# irkit_periph_lightFilter_v02.net
KiCad netlist of a schematic drawn in EAGLE
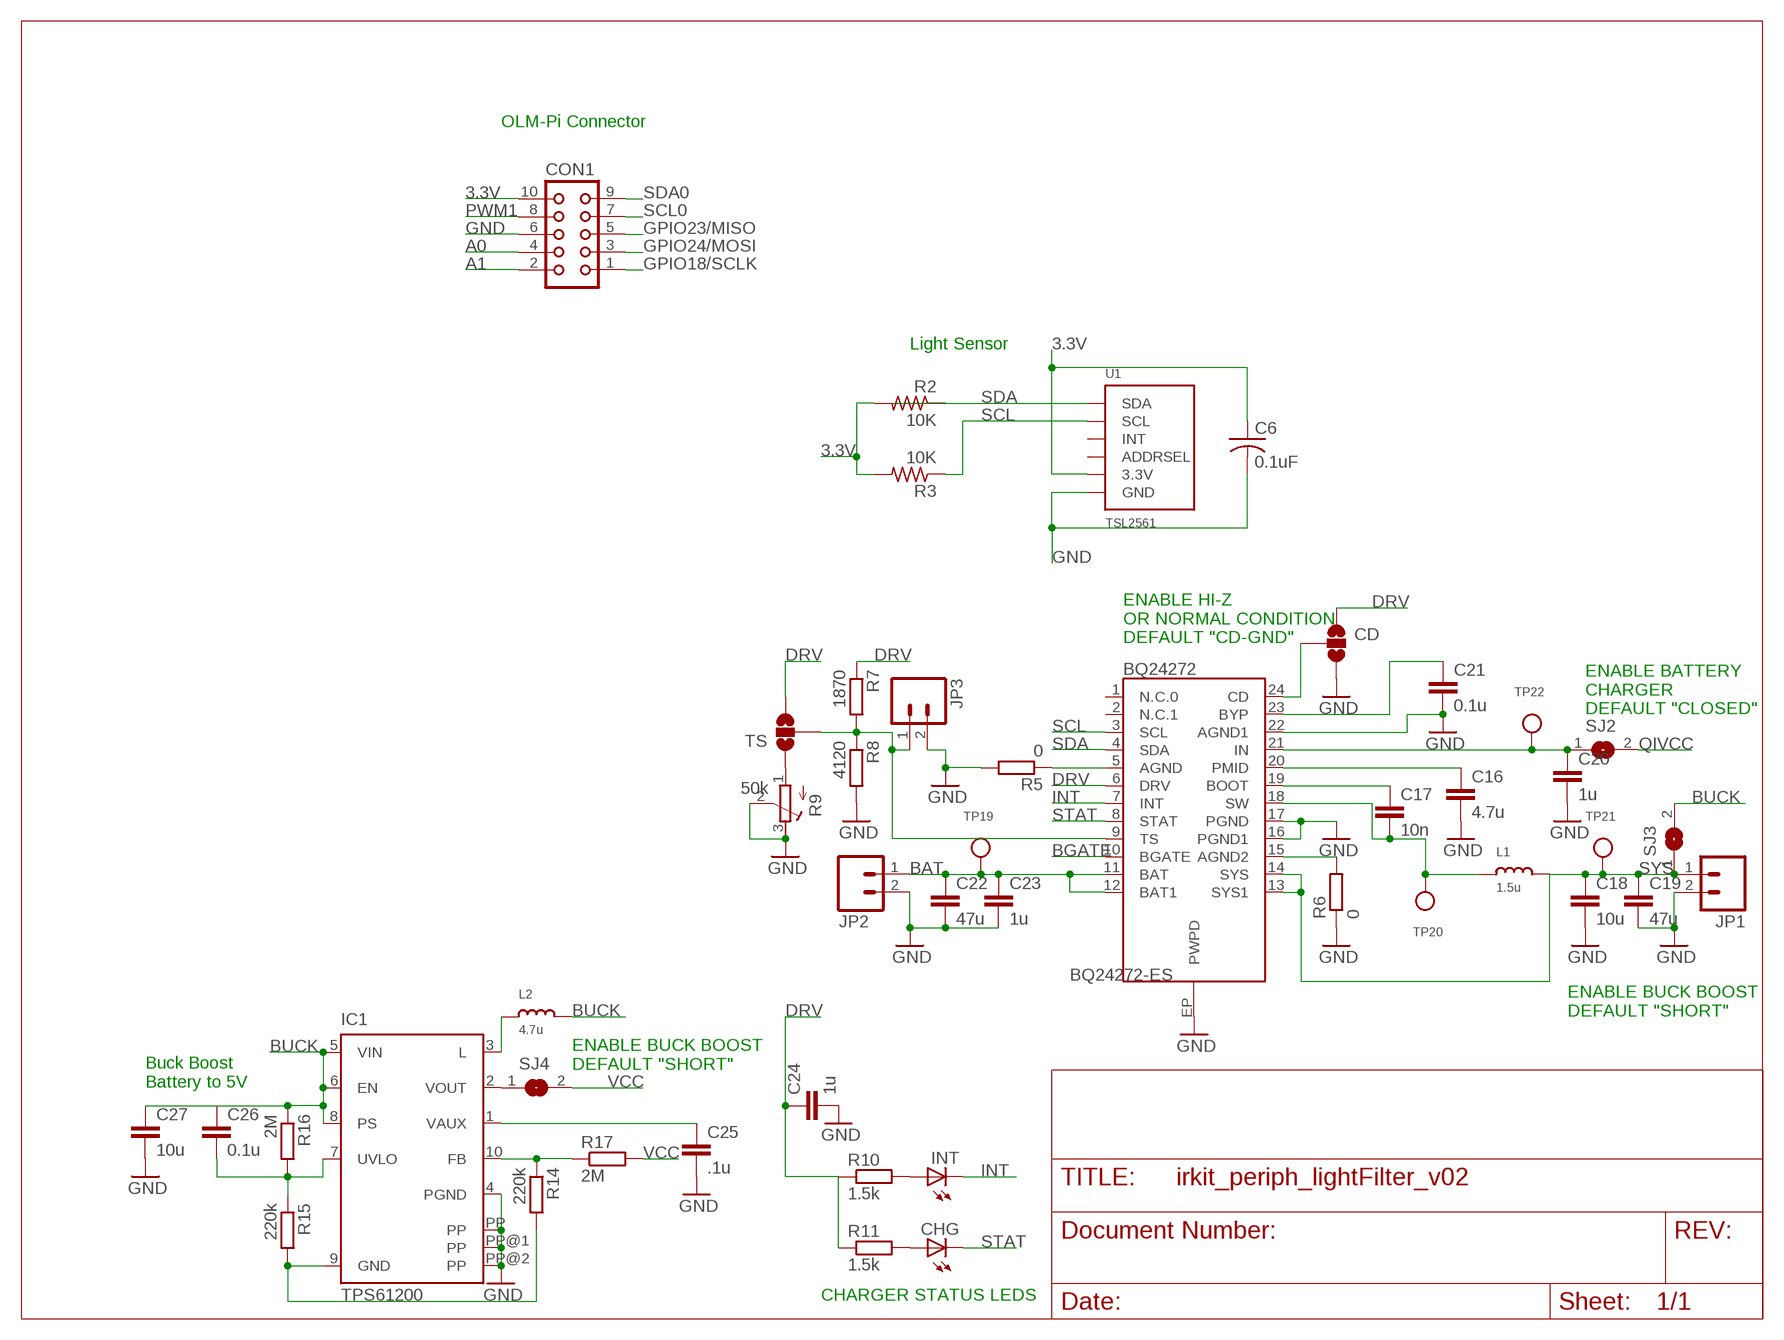
[diagram p0: schematic, sheet 1]

(export (version "E")
  (design (tool "Eeschema 10.0.6"))
  (components
    (comp (ref "BQ24272")
      (value "BQ24272-ES")
      (footprint "eagle-import:QFN-24_ALT2")
      (libsource (lib "eagle-import") (part "BQ24272-ES"))
    )
    (comp (ref "C6")
      (value "0.1uF")
      (footprint "eagle-import:C0805")
      (libsource (lib "eagle-import") (part "C-USC0805"))
    )
    (comp (ref "C16")
      (value "4.7u")
      (footprint "eagle-import:C0603K")
      (libsource (lib "eagle-import") (part "C-EUC0603K"))
    )
    (comp (ref "C17")
      (value "10n")
      (footprint "eagle-import:C0603K")
      (libsource (lib "eagle-import") (part "C-EUC0603K"))
    )
    (comp (ref "C18")
      (value "10u")
      (footprint "eagle-import:C0603K")
      (libsource (lib "eagle-import") (part "C-EUC0603K"))
    )
    (comp (ref "C19")
      (value "47u")
      (footprint "eagle-import:C0603K")
      (libsource (lib "eagle-import") (part "C-EUC0603K"))
    )
    (comp (ref "C20")
      (value "1u")
      (footprint "eagle-import:C0603K")
      (libsource (lib "eagle-import") (part "C-EUC0603K"))
    )
    (comp (ref "C21")
      (value "0.1u")
      (footprint "eagle-import:C0603K")
      (libsource (lib "eagle-import") (part "C-EUC0603K"))
    )
    (comp (ref "C22")
      (value "47u")
      (footprint "eagle-import:C0603K")
      (libsource (lib "eagle-import") (part "C-EUC0603K"))
    )
    (comp (ref "C23")
      (value "1u")
      (footprint "eagle-import:C0603K")
      (libsource (lib "eagle-import") (part "C-EUC0603K"))
    )
    (comp (ref "C24")
      (value "1u")
      (footprint "eagle-import:C0603K")
      (libsource (lib "eagle-import") (part "C-EUC0603K"))
    )
    (comp (ref "C25")
      (value ".1u")
      (footprint "eagle-import:C0603K")
      (libsource (lib "eagle-import") (part "C-EUC0603K"))
    )
    (comp (ref "C26")
      (value "0.1u")
      (footprint "eagle-import:C0603K")
      (libsource (lib "eagle-import") (part "C-EUC0603K"))
    )
    (comp (ref "C27")
      (value "10u")
      (footprint "eagle-import:C0603K")
      (libsource (lib "eagle-import") (part "C-EUC0603K"))
    )
    (comp (ref "CD")
      (value "SOLDERJUMPER_2WAYS")
      (footprint "eagle-import:SJ_3")
      (libsource (lib "eagle-import") (part "SOLDERJUMPER_2WAYS"))
    )
    (comp (ref "CHG")
      (value "LEDCHIP-LED0603")
      (footprint "eagle-import:CHIP-LED0603")
      (libsource (lib "eagle-import") (part "LEDCHIP-LED0603"))
    )
    (comp (ref "CON1")
      (value "CON10L")
      (footprint "eagle-import:CON10L")
      (libsource (lib "eagle-import") (part "CON10L"))
    )
    (comp (ref "IC1")
      (value "TPS61200")
      (footprint "eagle-import:S-PDSO-N10")
      (fields (field (name "MPN") "TPS61200DRCT"))
      (libsource (lib "eagle-import") (part "TPS61200"))
    )
    (comp (ref "INT")
      (value "LEDCHIP-LED0603")
      (footprint "eagle-import:CHIP-LED0603")
      (libsource (lib "eagle-import") (part "LEDCHIP-LED0603"))
    )
    (comp (ref "JP1")
      (value "M02PTH3")
      (footprint "eagle-import:1X02_LONGPADS")
      (libsource (lib "eagle-import") (part "M02PTH3"))
    )
    (comp (ref "JP2")
      (value "M02PTH3")
      (footprint "eagle-import:1X02_LONGPADS")
      (libsource (lib "eagle-import") (part "M02PTH3"))
    )
    (comp (ref "JP3")
      (value "M02PTH3")
      (footprint "eagle-import:1X02_LONGPADS")
      (libsource (lib "eagle-import") (part "M02PTH3"))
    )
    (comp (ref "L1")
      (value "1.5u")
      (footprint "eagle-import:INDUCTOR_5X5MM_NR5040_NOTHERMALS")
      (libsource (lib "eagle-import") (part "INDUCTORNR5040"))
    )
    (comp (ref "L2")
      (value "4.7u")
      (footprint "eagle-import:INDUCTOR_5X5MM_NR5040_NOTHERMALS")
      (libsource (lib "eagle-import") (part "INDUCTORNR5040"))
    )
    (comp (ref "R2")
      (value "10K")
      (footprint "eagle-import:R0805")
      (libsource (lib "eagle-import") (part "R-US_R0805"))
    )
    (comp (ref "R3")
      (value "10K")
      (footprint "eagle-import:R0805")
      (libsource (lib "eagle-import") (part "R-US_R0805"))
    )
    (comp (ref "R5")
      (value "0")
      (footprint "eagle-import:R0402")
      (fields (field (name "MPN") "ERJ3EKF3000V"))
      (libsource (lib "eagle-import") (part "R-EU_R0402"))
    )
    (comp (ref "R6")
      (value "0")
      (footprint "eagle-import:R0402")
      (fields (field (name "MPN") "ERJ3EKF3000V"))
      (libsource (lib "eagle-import") (part "R-EU_R0402"))
    )
    (comp (ref "R7")
      (value "1870")
      (footprint "eagle-import:R0402")
      (fields (field (name "MPN") "ERJ3EKF3000V"))
      (libsource (lib "eagle-import") (part "R-EU_R0402"))
    )
    (comp (ref "R8")
      (value "4120")
      (footprint "eagle-import:R0402")
      (fields (field (name "MPN") "ERJ3EKF3000V"))
      (libsource (lib "eagle-import") (part "R-EU_R0402"))
    )
    (comp (ref "R9")
      (value "50k")
      (footprint "eagle-import:RTRIM64Y")
      (libsource (lib "eagle-import") (part "R-TRIMM64Y"))
    )
    (comp (ref "R10")
      (value "1.5k")
      (footprint "eagle-import:R0402")
      (fields (field (name "MPN") "ERJ3EKF3000V"))
      (libsource (lib "eagle-import") (part "R-EU_R0402"))
    )
    (comp (ref "R11")
      (value "1.5k")
      (footprint "eagle-import:R0402")
      (fields (field (name "MPN") "ERJ3EKF3000V"))
      (libsource (lib "eagle-import") (part "R-EU_R0402"))
    )
    (comp (ref "R14")
      (value "220k")
      (footprint "eagle-import:R0402")
      (fields (field (name "MPN") "ERJ3EKF3000V"))
      (libsource (lib "eagle-import") (part "R-EU_R0402"))
    )
    (comp (ref "R15")
      (value "220k")
      (footprint "eagle-import:R0402")
      (fields (field (name "MPN") "ERJ3EKF3000V"))
      (libsource (lib "eagle-import") (part "R-EU_R0402"))
    )
    (comp (ref "R16")
      (value "2M")
      (footprint "eagle-import:R0402")
      (fields (field (name "MPN") "ERJ3EKF3000V"))
      (libsource (lib "eagle-import") (part "R-EU_R0402"))
    )
    (comp (ref "R17")
      (value "2M")
      (footprint "eagle-import:R0402")
      (fields (field (name "MPN") "ERJ3EKF3000V"))
      (libsource (lib "eagle-import") (part "R-EU_R0402"))
    )
    (comp (ref "SJ2") (value "SJ") (footprint "eagle-import:SJ") (libsource (lib "eagle-import") (part "SJ")))
    (comp (ref "SJ3") (value "SJ") (footprint "eagle-import:SJ") (libsource (lib "eagle-import") (part "SJ")))
    (comp (ref "SJ4") (value "SJ") (footprint "eagle-import:SJ") (libsource (lib "eagle-import") (part "SJ")))
    (comp (ref "TP19")
      (value "TESTPOINTROUND1MM")
      (footprint "eagle-import:TESTPOINT_ROUND_1MM")
      (libsource (lib "eagle-import") (part "TESTPOINTROUND1MM"))
    )
    (comp (ref "TP20")
      (value "TESTPOINTROUND1MM")
      (footprint "eagle-import:TESTPOINT_ROUND_1MM")
      (libsource (lib "eagle-import") (part "TESTPOINTROUND1MM"))
    )
    (comp (ref "TP21")
      (value "TESTPOINTROUND1MM")
      (footprint "eagle-import:TESTPOINT_ROUND_1MM")
      (libsource (lib "eagle-import") (part "TESTPOINTROUND1MM"))
    )
    (comp (ref "TP22")
      (value "TESTPOINTROUND1MM")
      (footprint "eagle-import:TESTPOINT_ROUND_1MM")
      (libsource (lib "eagle-import") (part "TESTPOINTROUND1MM"))
    )
    (comp (ref "TS")
      (value "SOLDERJUMPER_2WAYS")
      (footprint "eagle-import:SJ_3")
      (libsource (lib "eagle-import") (part "SOLDERJUMPER_2WAYS"))
    )
    (comp (ref "U1")
      (value "TSL2561")
      (footprint "eagle-import:TSL2561_FN")
      (libsource (lib "eagle-import") (part "TSL2561"))
    )
  )
  (nets
    (net (code "1") (name "/3.3V") (class "Default")
      (node (ref "C6") (pin "1") (pinfunction "1_1") (pintype "passive"))
      (node (ref "CON1") (pin "10") (pinfunction "10_10") (pintype "passive"))
      (node (ref "R2") (pin "2") (pinfunction "2_2") (pintype "passive"))
      (node (ref "R3") (pin "2") (pinfunction "2_2") (pintype "passive"))
      (node (ref "U1") (pin "VDD") (pinfunction "3.3V_VDD") (pintype "bidirectional"))
    )
    (net (code "2") (name "/A0") (class "Default")
      (node (ref "CON1") (pin "4") (pinfunction "4_4") (pintype "passive"))
    )
    (net (code "3") (name "/A1") (class "Default")
      (node (ref "CON1") (pin "2") (pinfunction "2_2") (pintype "passive"))
    )
    (net (code "4") (name "/BAT") (class "Default")
      (node (ref "BQ24272") (pin "11") (pinfunction "BAT_11") (pintype "bidirectional"))
      (node (ref "BQ24272") (pin "12") (pinfunction "BAT1_12") (pintype "bidirectional"))
      (node (ref "C22") (pin "1") (pinfunction "1_1") (pintype "passive"))
      (node (ref "C23") (pin "1") (pinfunction "1_1") (pintype "passive"))
      (node (ref "JP2") (pin "1") (pinfunction "1_1") (pintype "passive"))
      (node (ref "TP19") (pin "P$1") (pinfunction "P$1_P$1") (pintype "bidirectional"))
    )
    (net (code "5") (name "/BGATE") (class "Default")
      (node (ref "BQ24272") (pin "10") (pinfunction "BGATE_10") (pintype "bidirectional"))
    )
    (net (code "6") (name "/BUCK") (class "Default")
      (node (ref "C26") (pin "1") (pinfunction "1_1") (pintype "passive"))
      (node (ref "C27") (pin "1") (pinfunction "1_1") (pintype "passive"))
      (node (ref "IC1") (pin "5") (pinfunction "VIN_5") (pintype "input"))
      (node (ref "IC1") (pin "6") (pinfunction "EN_6") (pintype "input"))
      (node (ref "IC1") (pin "8") (pinfunction "PS_8") (pintype "input"))
      (node (ref "L2") (pin "P$2") (pinfunction "2_P$2") (pintype "passive"))
      (node (ref "R16") (pin "1") (pinfunction "1_1") (pintype "passive"))
      (node (ref "SJ3") (pin "2") (pinfunction "2_2") (pintype "passive"))
    )
    (net (code "7") (name "/DRV") (class "Default")
      (node (ref "BQ24272") (pin "6") (pinfunction "DRV_6") (pintype "bidirectional"))
      (node (ref "C24") (pin "1") (pinfunction "1_1") (pintype "passive"))
      (node (ref "CD") (pin "1") (pinfunction "1_1") (pintype "passive"))
      (node (ref "R10") (pin "1") (pinfunction "1_1") (pintype "passive"))
      (node (ref "R11") (pin "1") (pinfunction "1_1") (pintype "passive"))
      (node (ref "R7") (pin "1") (pinfunction "1_1") (pintype "passive"))
      (node (ref "TS") (pin "3") (pinfunction "3_3") (pintype "passive"))
    )
    (net (code "8") (name "/GPIO18{slash}SCLK") (class "Default")
      (node (ref "CON1") (pin "1") (pinfunction "1_1") (pintype "passive"))
    )
    (net (code "9") (name "/GPIO23{slash}MISO") (class "Default")
      (node (ref "CON1") (pin "5") (pinfunction "5_5") (pintype "passive"))
    )
    (net (code "10") (name "/GPIO24{slash}MOSI") (class "Default")
      (node (ref "CON1") (pin "3") (pinfunction "3_3") (pintype "passive"))
    )
    (net (code "11") (name "/INT") (class "Default")
      (node (ref "BQ24272") (pin "7") (pinfunction "INT_7") (pintype "bidirectional"))
      (node (ref "INT") (pin "C") (pinfunction "C_C") (pintype "passive"))
    )
    (net (code "12") (name "/PWM1") (class "Default")
      (node (ref "CON1") (pin "8") (pinfunction "8_8") (pintype "passive"))
    )
    (net (code "13") (name "/QIVCC") (class "Default")
      (node (ref "SJ2") (pin "2") (pinfunction "2_2") (pintype "passive"))
    )
    (net (code "14") (name "/SCL") (class "Default")
      (node (ref "BQ24272") (pin "3") (pinfunction "SCL_3") (pintype "bidirectional"))
      (node (ref "R3") (pin "1") (pinfunction "1_1") (pintype "passive"))
      (node (ref "U1") (pin "CLK") (pinfunction "SCL_CLK") (pintype "bidirectional"))
    )
    (net (code "15") (name "/SCL0") (class "Default")
      (node (ref "CON1") (pin "7") (pinfunction "7_7") (pintype "passive"))
    )
    (net (code "16") (name "/SDA") (class "Default")
      (node (ref "BQ24272") (pin "4") (pinfunction "SDA_4") (pintype "bidirectional"))
      (node (ref "R2") (pin "1") (pinfunction "1_1") (pintype "passive"))
      (node (ref "U1") (pin "DATA") (pinfunction "SDA_DATA") (pintype "bidirectional"))
    )
    (net (code "17") (name "/SDA0") (class "Default")
      (node (ref "CON1") (pin "9") (pinfunction "9_9") (pintype "passive"))
    )
    (net (code "18") (name "/STAT") (class "Default")
      (node (ref "BQ24272") (pin "8") (pinfunction "STAT_8") (pintype "bidirectional"))
      (node (ref "CHG") (pin "C") (pinfunction "C_C") (pintype "passive"))
    )
    (net (code "19") (name "/SYS") (class "Default")
      (node (ref "BQ24272") (pin "13") (pinfunction "SYS1_13") (pintype "bidirectional"))
      (node (ref "BQ24272") (pin "14") (pinfunction "SYS_14") (pintype "bidirectional"))
      (node (ref "C18") (pin "1") (pinfunction "1_1") (pintype "passive"))
      (node (ref "C19") (pin "1") (pinfunction "1_1") (pintype "passive"))
      (node (ref "JP1") (pin "1") (pinfunction "1_1") (pintype "passive"))
      (node (ref "L1") (pin "P$2") (pinfunction "2_P$2") (pintype "passive"))
      (node (ref "SJ3") (pin "1") (pinfunction "1_1") (pintype "passive"))
      (node (ref "TP21") (pin "P$1") (pinfunction "P$1_P$1") (pintype "bidirectional"))
    )
    (net (code "20") (name "/VCC") (class "Default")
      (node (ref "R17") (pin "2") (pinfunction "2_2") (pintype "passive"))
      (node (ref "SJ4") (pin "2") (pinfunction "2_2") (pintype "passive"))
    )
    (net (code "21") (name "GND") (class "Default")
      (node (ref "BQ24272") (pin "16") (pinfunction "PGND1_16") (pintype "bidirectional"))
      (node (ref "BQ24272") (pin "17") (pinfunction "PGND_17") (pintype "bidirectional"))
      (node (ref "BQ24272") (pin "22") (pinfunction "AGND1_22") (pintype "bidirectional"))
      (node (ref "BQ24272") (pin "EP") (pinfunction "PWPD_EP") (pintype "bidirectional"))
      (node (ref "C16") (pin "2") (pinfunction "2_2") (pintype "passive"))
      (node (ref "C18") (pin "2") (pinfunction "2_2") (pintype "passive"))
      (node (ref "C19") (pin "2") (pinfunction "2_2") (pintype "passive"))
      (node (ref "C20") (pin "2") (pinfunction "2_2") (pintype "passive"))
      (node (ref "C21") (pin "2") (pinfunction "2_2") (pintype "passive"))
      (node (ref "C22") (pin "2") (pinfunction "2_2") (pintype "passive"))
      (node (ref "C23") (pin "2") (pinfunction "2_2") (pintype "passive"))
      (node (ref "C24") (pin "2") (pinfunction "2_2") (pintype "passive"))
      (node (ref "C25") (pin "2") (pinfunction "2_2") (pintype "passive"))
      (node (ref "C27") (pin "2") (pinfunction "2_2") (pintype "passive"))
      (node (ref "C6") (pin "2") (pinfunction "2_2") (pintype "passive"))
      (node (ref "CD") (pin "3") (pinfunction "3_3") (pintype "passive"))
      (node (ref "CON1") (pin "6") (pinfunction "6_6") (pintype "passive"))
      (node (ref "IC1") (pin "4") (pinfunction "PGND_4") (pintype "power_in"))
      (node (ref "IC1") (pin "PP") (pinfunction "PP_PP") (pintype "power_in"))
      (node (ref "IC1") (pin "PP@1") (pinfunction "PP_PP@1") (pintype "power_in"))
      (node (ref "IC1") (pin "PP@2") (pinfunction "PP_PP@2") (pintype "power_in"))
      (node (ref "JP1") (pin "2") (pinfunction "2_2") (pintype "passive"))
      (node (ref "JP2") (pin "2") (pinfunction "2_2") (pintype "passive"))
      (node (ref "JP3") (pin "2") (pinfunction "2_2") (pintype "passive"))
      (node (ref "R5") (pin "2") (pinfunction "2_2") (pintype "passive"))
      (node (ref "R6") (pin "1") (pinfunction "1_1") (pintype "passive"))
      (node (ref "R8") (pin "2") (pinfunction "2_2") (pintype "passive"))
      (node (ref "R9") (pin "2") (pinfunction "S_2") (pintype "passive"))
      (node (ref "R9") (pin "3") (pinfunction "E_3") (pintype "passive"))
      (node (ref "U1") (pin "VSS") (pinfunction "GND_VSS") (pintype "bidirectional"))
    )
    (net (code "22") (name "Net-(BQ24272-AGND)") (class "Default")
      (node (ref "BQ24272") (pin "5") (pinfunction "AGND_5") (pintype "bidirectional"))
      (node (ref "R5") (pin "1") (pinfunction "1_1") (pintype "passive"))
    )
    (net (code "23") (name "Net-(BQ24272-AGND2)") (class "Default")
      (node (ref "BQ24272") (pin "15") (pinfunction "AGND2_15") (pintype "bidirectional"))
      (node (ref "R6") (pin "2") (pinfunction "2_2") (pintype "passive"))
    )
    (net (code "24") (name "Net-(BQ24272-BOOT)") (class "Default")
      (node (ref "BQ24272") (pin "19") (pinfunction "BOOT_19") (pintype "bidirectional"))
      (node (ref "C17") (pin "1") (pinfunction "1_1") (pintype "passive"))
    )
    (net (code "25") (name "Net-(BQ24272-BYP)") (class "Default")
      (node (ref "BQ24272") (pin "23") (pinfunction "BYP_23") (pintype "bidirectional"))
      (node (ref "C21") (pin "1") (pinfunction "1_1") (pintype "passive"))
    )
    (net (code "26") (name "Net-(BQ24272-CD)") (class "Default")
      (node (ref "BQ24272") (pin "24") (pinfunction "CD_24") (pintype "bidirectional"))
      (node (ref "CD") (pin "2") (pinfunction "2_2") (pintype "passive"))
    )
    (net (code "27") (name "Net-(BQ24272-IN)") (class "Default")
      (node (ref "BQ24272") (pin "21") (pinfunction "IN_21") (pintype "bidirectional"))
      (node (ref "C20") (pin "1") (pinfunction "1_1") (pintype "passive"))
      (node (ref "SJ2") (pin "1") (pinfunction "1_1") (pintype "passive"))
      (node (ref "TP22") (pin "P$1") (pinfunction "P$1_P$1") (pintype "bidirectional"))
    )
    (net (code "28") (name "Net-(BQ24272-PMID)") (class "Default")
      (node (ref "BQ24272") (pin "20") (pinfunction "PMID_20") (pintype "bidirectional"))
      (node (ref "C16") (pin "1") (pinfunction "1_1") (pintype "passive"))
    )
    (net (code "29") (name "Net-(BQ24272-SW)") (class "Default")
      (node (ref "BQ24272") (pin "18") (pinfunction "SW_18") (pintype "bidirectional"))
      (node (ref "C17") (pin "2") (pinfunction "2_2") (pintype "passive"))
      (node (ref "L1") (pin "P$1") (pinfunction "1_P$1") (pintype "passive"))
      (node (ref "TP20") (pin "P$1") (pinfunction "P$1_P$1") (pintype "bidirectional"))
    )
    (net (code "30") (name "Net-(BQ24272-TS)") (class "Default")
      (node (ref "BQ24272") (pin "9") (pinfunction "TS_9") (pintype "bidirectional"))
      (node (ref "JP3") (pin "1") (pinfunction "1_1") (pintype "passive"))
      (node (ref "R7") (pin "2") (pinfunction "2_2") (pintype "passive"))
      (node (ref "R8") (pin "1") (pinfunction "1_1") (pintype "passive"))
      (node (ref "TS") (pin "2") (pinfunction "2_2") (pintype "passive"))
    )
    (net (code "31") (name "Net-(CHG-PadA)") (class "Default")
      (node (ref "CHG") (pin "A") (pinfunction "A_A") (pintype "passive"))
      (node (ref "R11") (pin "2") (pinfunction "2_2") (pintype "passive"))
    )
    (net (code "32") (name "Net-(IC1-FB)") (class "Default")
      (node (ref "IC1") (pin "10") (pinfunction "FB_10") (pintype "input"))
      (node (ref "R14") (pin "1") (pinfunction "1_1") (pintype "passive"))
      (node (ref "R17") (pin "1") (pinfunction "1_1") (pintype "passive"))
    )
    (net (code "33") (name "Net-(IC1-GND)") (class "Default")
      (node (ref "IC1") (pin "9") (pinfunction "GND_9") (pintype "power_in"))
      (node (ref "R14") (pin "2") (pinfunction "2_2") (pintype "passive"))
      (node (ref "R15") (pin "2") (pinfunction "2_2") (pintype "passive"))
    )
    (net (code "34") (name "Net-(IC1-L)") (class "Default")
      (node (ref "IC1") (pin "3") (pinfunction "L_3") (pintype "input"))
      (node (ref "L2") (pin "P$1") (pinfunction "1_P$1") (pintype "passive"))
    )
    (net (code "35") (name "Net-(IC1-UVLO)") (class "Default")
      (node (ref "C26") (pin "2") (pinfunction "2_2") (pintype "passive"))
      (node (ref "IC1") (pin "7") (pinfunction "UVLO_7") (pintype "input"))
      (node (ref "R15") (pin "1") (pinfunction "1_1") (pintype "passive"))
      (node (ref "R16") (pin "2") (pinfunction "2_2") (pintype "passive"))
    )
    (net (code "36") (name "Net-(IC1-VAUX)") (class "Default")
      (node (ref "C25") (pin "1") (pinfunction "1_1") (pintype "passive"))
      (node (ref "IC1") (pin "1") (pinfunction "VAUX_1") (pintype "bidirectional"))
    )
    (net (code "37") (name "Net-(IC1-VOUT)") (class "Default")
      (node (ref "IC1") (pin "2") (pinfunction "VOUT_2") (pintype "passive"))
      (node (ref "SJ4") (pin "1") (pinfunction "1_1") (pintype "passive"))
    )
    (net (code "38") (name "Net-(INT-PadA)") (class "Default")
      (node (ref "INT") (pin "A") (pinfunction "A_A") (pintype "passive"))
      (node (ref "R10") (pin "2") (pinfunction "2_2") (pintype "passive"))
    )
    (net (code "39") (name "Net-(R9-A)") (class "Default")
      (node (ref "R9") (pin "1") (pinfunction "A_1") (pintype "passive"))
      (node (ref "TS") (pin "1") (pinfunction "1_1") (pintype "passive"))
    )
    (net (code "40") (name "unconnected-(BQ24272-N.C.0-Pad1)") (class "Default")
      (node (ref "BQ24272") (pin "1") (pinfunction "N.C.0_1") (pintype "bidirectional"))
    )
    (net (code "41") (name "unconnected-(BQ24272-N.C.1-Pad2)") (class "Default")
      (node (ref "BQ24272") (pin "2") (pinfunction "N.C.1_2") (pintype "bidirectional"))
    )
    (net (code "42") (name "unconnected-(U1-ADDRSEL-PadADR)") (class "Default")
      (node (ref "U1") (pin "ADR") (pinfunction "ADDRSEL_ADR") (pintype "bidirectional"))
    )
    (net (code "43") (name "unconnected-(U1-PadINT)") (class "Default")
      (node (ref "U1") (pin "INT") (pinfunction "INT_INT") (pintype "bidirectional"))
    )
  )
)
